# Output-Connectors.net
KiCad netlist of a schematic drawn in Altium Designer
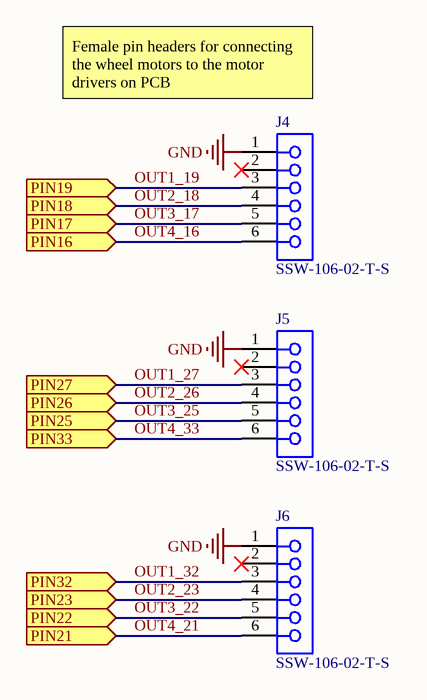
[diagram p0: Output-Connectors.SchDoc]

(export (version "E")
  (design (tool "Eeschema 10.0.6"))
  (components
    (comp (ref "J4")
      (value "SSW-106-02-T-S")
      (footprint "SMTC-SSW-106-02-X-S")
      (description "SQ Post Socket, Through-hole, Vertical, -55 to 105 degC, 2.54mm Pitch, 6-Pin, Female, RoHS")
      (fields (field (name "MANUFACTURER") "Samtec"))
      (libsource (lib "Altium Content Vault") (part "SMTC-SSW-106-02-X-S-X"))
    )
    (comp (ref "J5")
      (value "SSW-106-02-T-S")
      (footprint "SMTC-SSW-106-02-X-S")
      (description "SQ Post Socket, Through-hole, Vertical, -55 to 105 degC, 2.54mm Pitch, 6-Pin, Female, RoHS")
      (fields (field (name "MANUFACTURER") "Samtec"))
      (libsource (lib "Altium Content Vault") (part "SMTC-SSW-106-02-X-S-X"))
    )
    (comp (ref "J6")
      (value "SSW-106-02-T-S")
      (footprint "SMTC-SSW-106-02-X-S")
      (description "SQ Post Socket, Through-hole, Vertical, -55 to 105 degC, 2.54mm Pitch, 6-Pin, Female, RoHS")
      (fields (field (name "MANUFACTURER") "Samtec"))
      (libsource (lib "Altium Content Vault") (part "SMTC-SSW-106-02-X-S-X"))
    )
  )
  (nets
    (net (code "1") (name "/OUT1_19") (class "Default")
      (node (ref "J4") (pin "3") (pinfunction "3_3") (pintype "passive"))
    )
    (net (code "2") (name "/OUT1_27") (class "Default")
      (node (ref "J5") (pin "3") (pinfunction "3_3") (pintype "passive"))
    )
    (net (code "3") (name "/OUT1_32") (class "Default")
      (node (ref "J6") (pin "3") (pinfunction "3_3") (pintype "passive"))
    )
    (net (code "4") (name "/OUT2_18") (class "Default")
      (node (ref "J4") (pin "4") (pinfunction "4_4") (pintype "passive"))
    )
    (net (code "5") (name "/OUT2_23") (class "Default")
      (node (ref "J6") (pin "4") (pinfunction "4_4") (pintype "passive"))
    )
    (net (code "6") (name "/OUT2_26") (class "Default")
      (node (ref "J5") (pin "4") (pinfunction "4_4") (pintype "passive"))
    )
    (net (code "7") (name "/OUT3_17") (class "Default")
      (node (ref "J4") (pin "5") (pinfunction "5_5") (pintype "passive"))
    )
    (net (code "8") (name "/OUT3_22") (class "Default")
      (node (ref "J6") (pin "5") (pinfunction "5_5") (pintype "passive"))
    )
    (net (code "9") (name "/OUT3_25") (class "Default")
      (node (ref "J5") (pin "5") (pinfunction "5_5") (pintype "passive"))
    )
    (net (code "10") (name "/OUT4_16") (class "Default")
      (node (ref "J4") (pin "6") (pinfunction "6_6") (pintype "passive"))
    )
    (net (code "11") (name "/OUT4_21") (class "Default")
      (node (ref "J6") (pin "6") (pinfunction "6_6") (pintype "passive"))
    )
    (net (code "12") (name "/OUT4_33") (class "Default")
      (node (ref "J5") (pin "6") (pinfunction "6_6") (pintype "passive"))
    )
    (net (code "13") (name "GND") (class "Default")
      (node (ref "J4") (pin "1") (pinfunction "1_1") (pintype "passive"))
      (node (ref "J5") (pin "1") (pinfunction "1_1") (pintype "passive"))
      (node (ref "J6") (pin "1") (pinfunction "1_1") (pintype "passive"))
    )
    (net (code "14") (name "unconnected-(J4-Pad2)") (class "Default")
      (node (ref "J4") (pin "2") (pinfunction "2_2") (pintype "passive+no_connect"))
    )
    (net (code "15") (name "unconnected-(J5-Pad2)") (class "Default")
      (node (ref "J5") (pin "2") (pinfunction "2_2") (pintype "passive+no_connect"))
    )
    (net (code "16") (name "unconnected-(J6-Pad2)") (class "Default")
      (node (ref "J6") (pin "2") (pinfunction "2_2") (pintype "passive+no_connect"))
    )
  )
)
